# ADCMP607-step-gen.net
KiCad netlist of a schematic drawn in EAGLE
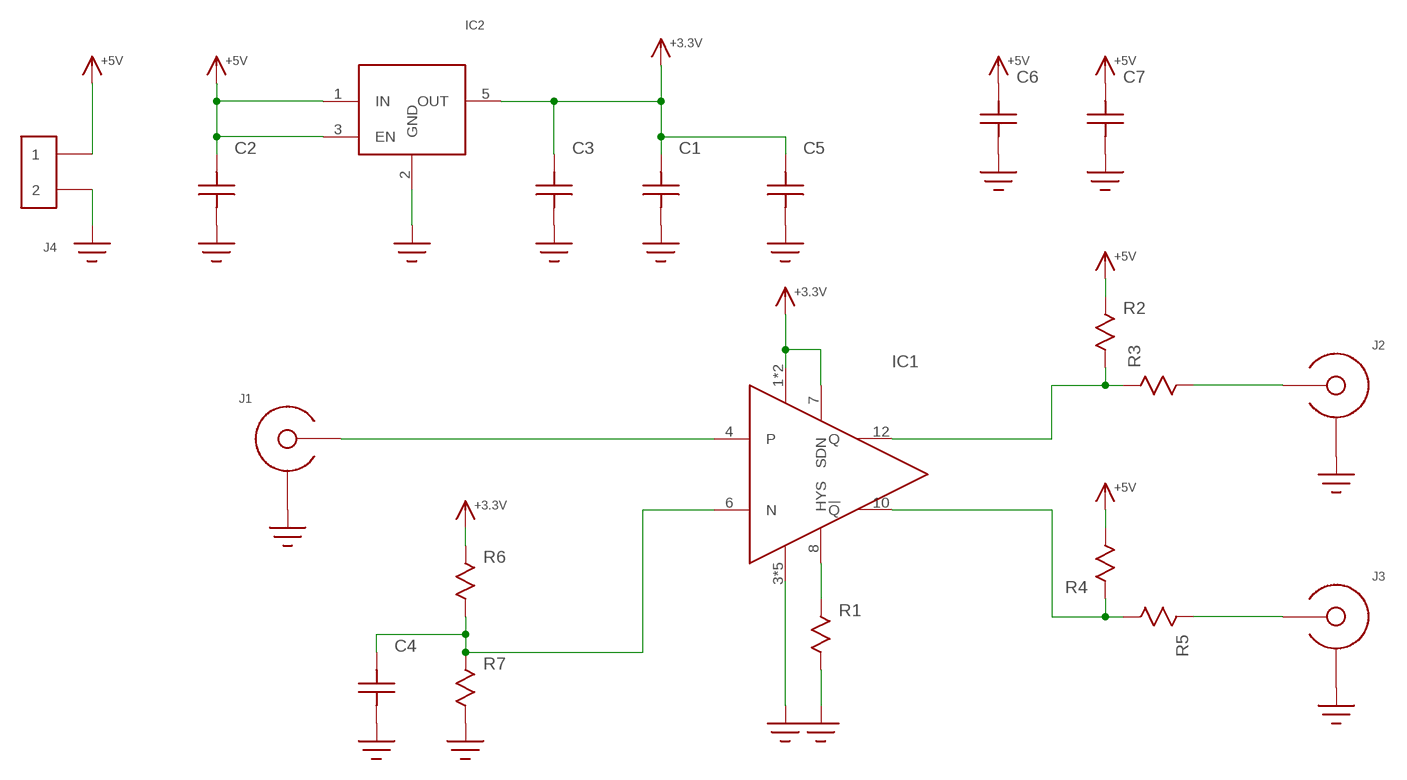
[diagram p0: schematic, sheet 1]

(export (version "E")
  (design (tool "Eeschema 10.0.6"))
  (components
    (comp (ref "C1") (value "C") (footprint "eagle-import:C0402") (libsource (lib "eagle-import") (part "C")))
    (comp (ref "C2")
      (value "C1206")
      (footprint "eagle-import:1206")
      (libsource (lib "eagle-import") (part "C1206"))
    )
    (comp (ref "C3")
      (value "C0603")
      (footprint "eagle-import:C0603")
      (libsource (lib "eagle-import") (part "C0603"))
    )
    (comp (ref "C4")
      (value "C0603")
      (footprint "eagle-import:C0603")
      (libsource (lib "eagle-import") (part "C0603"))
    )
    (comp (ref "C5") (value "C") (footprint "eagle-import:C0402") (libsource (lib "eagle-import") (part "C")))
    (comp (ref "C6") (value "C") (footprint "eagle-import:C0402") (libsource (lib "eagle-import") (part "C")))
    (comp (ref "C7") (value "C") (footprint "eagle-import:C0402") (libsource (lib "eagle-import") (part "C")))
    (comp (ref "IC1")
      (value "ADCMP607")
      (footprint "eagle-import:QFN12-3X3")
      (libsource (lib "eagle-import") (part "ADCMP607"))
    )
    (comp (ref "IC2")
      (value "MIC5501")
      (footprint "eagle-import:SOT23-5")
      (libsource (lib "eagle-import") (part "MIC5501"))
    )
    (comp (ref "J1")
      (value "SMA-EDGE-LAUNCH4L-4020-TAPER-FIXED")
      (footprint "eagle-import:SMA_EDGE_LAUNCH_4L_4020_TAPER_FIXED")
      (libsource (lib "eagle-import") (part "SMA-EDGE-LAUNCH4L-4020-TAPER-FIXED"))
    )
    (comp (ref "J2")
      (value "SMA-EDGE-LAUNCH4L-4020-TAPER-FIXED")
      (footprint "eagle-import:SMA_EDGE_LAUNCH_4L_4020_TAPER_FIXED")
      (libsource (lib "eagle-import") (part "SMA-EDGE-LAUNCH4L-4020-TAPER-FIXED"))
    )
    (comp (ref "J3")
      (value "SMA-EDGE-LAUNCH4L-4020-TAPER-FIXED")
      (footprint "eagle-import:SMA_EDGE_LAUNCH_4L_4020_TAPER_FIXED")
      (libsource (lib "eagle-import") (part "SMA-EDGE-LAUNCH4L-4020-TAPER-FIXED"))
    )
    (comp (ref "J4")
      (value "HEADER_2PIN")
      (footprint "eagle-import:HEADER_2PIN")
      (libsource (lib "eagle-import") (part "HEADER_2PIN"))
    )
    (comp (ref "R1")
      (value "R0603")
      (footprint "eagle-import:R0603")
      (libsource (lib "eagle-import") (part "R0603"))
    )
    (comp (ref "R2")
      (value "R0402")
      (footprint "eagle-import:0402")
      (libsource (lib "eagle-import") (part "R0402"))
    )
    (comp (ref "R3")
      (value "R0402")
      (footprint "eagle-import:0402")
      (libsource (lib "eagle-import") (part "R0402"))
    )
    (comp (ref "R4")
      (value "R0402")
      (footprint "eagle-import:0402")
      (libsource (lib "eagle-import") (part "R0402"))
    )
    (comp (ref "R5")
      (value "R0402")
      (footprint "eagle-import:0402")
      (libsource (lib "eagle-import") (part "R0402"))
    )
    (comp (ref "R6")
      (value "R0603")
      (footprint "eagle-import:R0603")
      (libsource (lib "eagle-import") (part "R0603"))
    )
    (comp (ref "R7")
      (value "R0603")
      (footprint "eagle-import:R0603")
      (libsource (lib "eagle-import") (part "R0603"))
    )
  )
  (nets
    (net (code "1") (name "+3.3V") (class "Default")
      (node (ref "C1") (pin "2") (pinfunction "P$2_2") (pintype "bidirectional"))
      (node (ref "C3") (pin "P$2") (pinfunction "P$2_P$2") (pintype "bidirectional"))
      (node (ref "C5") (pin "2") (pinfunction "P$2_2") (pintype "bidirectional"))
      (node (ref "IC1") (pin "1") (pinfunction "VCC_1") (pintype "bidirectional"))
      (node (ref "IC1") (pin "2") (pinfunction "VCC_2") (pintype "bidirectional"))
      (node (ref "IC1") (pin "7") (pinfunction "SDN_7") (pintype "bidirectional"))
      (node (ref "IC2") (pin "5") (pinfunction "OUT_5") (pintype "bidirectional"))
      (node (ref "R6") (pin "P$1") (pinfunction "P$3_P$1") (pintype "bidirectional"))
    )
    (net (code "2") (name "+5V") (class "Default")
      (node (ref "C2") (pin "P$2") (pinfunction "P$2_P$2") (pintype "bidirectional"))
      (node (ref "C6") (pin "2") (pinfunction "P$2_2") (pintype "bidirectional"))
      (node (ref "C7") (pin "2") (pinfunction "P$2_2") (pintype "bidirectional"))
      (node (ref "IC2") (pin "1") (pinfunction "IN_1") (pintype "bidirectional"))
      (node (ref "IC2") (pin "3") (pinfunction "EN_3") (pintype "bidirectional"))
      (node (ref "J4") (pin "1") (pinfunction "1_1") (pintype "bidirectional"))
      (node (ref "R2") (pin "1") (pinfunction "P$3_1") (pintype "bidirectional"))
      (node (ref "R4") (pin "2") (pinfunction "P$4_2") (pintype "bidirectional"))
    )
    (net (code "3") (name "GND") (class "Default")
      (node (ref "C1") (pin "1") (pinfunction "P$1_1") (pintype "bidirectional"))
      (node (ref "C2") (pin "P$1") (pinfunction "P$1_P$1") (pintype "bidirectional"))
      (node (ref "C3") (pin "P$1") (pinfunction "P$1_P$1") (pintype "bidirectional"))
      (node (ref "C4") (pin "P$1") (pinfunction "P$1_P$1") (pintype "bidirectional"))
      (node (ref "C5") (pin "1") (pinfunction "P$1_1") (pintype "bidirectional"))
      (node (ref "C6") (pin "1") (pinfunction "P$1_1") (pintype "bidirectional"))
      (node (ref "C7") (pin "1") (pinfunction "P$1_1") (pintype "bidirectional"))
      (node (ref "IC1") (pin "11") (pinfunction "VEE_11") (pintype "bidirectional"))
      (node (ref "IC1") (pin "3") (pinfunction "VEE_3") (pintype "bidirectional"))
      (node (ref "IC1") (pin "5") (pinfunction "VEE_5") (pintype "bidirectional"))
      (node (ref "IC1") (pin "9") (pinfunction "VEE_9") (pintype "bidirectional"))
      (node (ref "IC1") (pin "EP") (pinfunction "VEE_EP") (pintype "bidirectional"))
      (node (ref "IC2") (pin "2") (pinfunction "GND_2") (pintype "bidirectional"))
      (node (ref "J1") (pin "BOTTOM_GND") (pinfunction "SHIELD_BOTTOM_GND") (pintype "bidirectional"))
      (node (ref "J1") (pin "GND@1") (pinfunction "SHIELD_GND@1") (pintype "bidirectional"))
      (node (ref "J1") (pin "GND@14") (pinfunction "SHIELD_GND@14") (pintype "bidirectional"))
      (node (ref "J1") (pin "GND@15") (pinfunction "SHIELD_GND@15") (pintype "bidirectional"))
      (node (ref "J1") (pin "GND@16") (pinfunction "SHIELD_GND@16") (pintype "bidirectional"))
      (node (ref "J1") (pin "GND@17") (pinfunction "SHIELD_GND@17") (pintype "bidirectional"))
      (node (ref "J1") (pin "GND@2") (pinfunction "SHIELD_GND@2") (pintype "bidirectional"))
      (node (ref "J1") (pin "GND@3") (pinfunction "SHIELD_GND@3") (pintype "bidirectional"))
      (node (ref "J1") (pin "GND@4") (pinfunction "SHIELD_GND@4") (pintype "bidirectional"))
      (node (ref "J1") (pin "GND@5") (pinfunction "SHIELD_GND@5") (pintype "bidirectional"))
      (node (ref "J1") (pin "GND@6") (pinfunction "SHIELD_GND@6") (pintype "bidirectional"))
      (node (ref "J1") (pin "GND@7") (pinfunction "SHIELD_GND@7") (pintype "bidirectional"))
      (node (ref "J1") (pin "GND@8") (pinfunction "SHIELD_GND@8") (pintype "bidirectional"))
      (node (ref "J1") (pin "GND_PAD1") (pinfunction "SHIELD_GND_PAD1") (pintype "bidirectional"))
      (node (ref "J1") (pin "GND_PAD2") (pinfunction "SHIELD_GND_PAD2") (pintype "bidirectional"))
      (node (ref "J1") (pin "P$1") (pinfunction "SHIELD_P$1") (pintype "bidirectional"))
      (node (ref "J1") (pin "P$2") (pinfunction "SHIELD_P$2") (pintype "bidirectional"))
      (node (ref "J2") (pin "BOTTOM_GND") (pinfunction "SHIELD_BOTTOM_GND") (pintype "bidirectional"))
      (node (ref "J2") (pin "GND@1") (pinfunction "SHIELD_GND@1") (pintype "bidirectional"))
      (node (ref "J2") (pin "GND@14") (pinfunction "SHIELD_GND@14") (pintype "bidirectional"))
      (node (ref "J2") (pin "GND@15") (pinfunction "SHIELD_GND@15") (pintype "bidirectional"))
      (node (ref "J2") (pin "GND@16") (pinfunction "SHIELD_GND@16") (pintype "bidirectional"))
      (node (ref "J2") (pin "GND@17") (pinfunction "SHIELD_GND@17") (pintype "bidirectional"))
      (node (ref "J2") (pin "GND@2") (pinfunction "SHIELD_GND@2") (pintype "bidirectional"))
      (node (ref "J2") (pin "GND@3") (pinfunction "SHIELD_GND@3") (pintype "bidirectional"))
      (node (ref "J2") (pin "GND@4") (pinfunction "SHIELD_GND@4") (pintype "bidirectional"))
      (node (ref "J2") (pin "GND@5") (pinfunction "SHIELD_GND@5") (pintype "bidirectional"))
      (node (ref "J2") (pin "GND@6") (pinfunction "SHIELD_GND@6") (pintype "bidirectional"))
      (node (ref "J2") (pin "GND@7") (pinfunction "SHIELD_GND@7") (pintype "bidirectional"))
      (node (ref "J2") (pin "GND@8") (pinfunction "SHIELD_GND@8") (pintype "bidirectional"))
      (node (ref "J2") (pin "GND_PAD1") (pinfunction "SHIELD_GND_PAD1") (pintype "bidirectional"))
      (node (ref "J2") (pin "GND_PAD2") (pinfunction "SHIELD_GND_PAD2") (pintype "bidirectional"))
      (node (ref "J2") (pin "P$1") (pinfunction "SHIELD_P$1") (pintype "bidirectional"))
      (node (ref "J2") (pin "P$2") (pinfunction "SHIELD_P$2") (pintype "bidirectional"))
      (node (ref "J3") (pin "BOTTOM_GND") (pinfunction "SHIELD_BOTTOM_GND") (pintype "bidirectional"))
      (node (ref "J3") (pin "GND@1") (pinfunction "SHIELD_GND@1") (pintype "bidirectional"))
      (node (ref "J3") (pin "GND@14") (pinfunction "SHIELD_GND@14") (pintype "bidirectional"))
      (node (ref "J3") (pin "GND@15") (pinfunction "SHIELD_GND@15") (pintype "bidirectional"))
      (node (ref "J3") (pin "GND@16") (pinfunction "SHIELD_GND@16") (pintype "bidirectional"))
      (node (ref "J3") (pin "GND@17") (pinfunction "SHIELD_GND@17") (pintype "bidirectional"))
      (node (ref "J3") (pin "GND@2") (pinfunction "SHIELD_GND@2") (pintype "bidirectional"))
      (node (ref "J3") (pin "GND@3") (pinfunction "SHIELD_GND@3") (pintype "bidirectional"))
      (node (ref "J3") (pin "GND@4") (pinfunction "SHIELD_GND@4") (pintype "bidirectional"))
      (node (ref "J3") (pin "GND@5") (pinfunction "SHIELD_GND@5") (pintype "bidirectional"))
      (node (ref "J3") (pin "GND@6") (pinfunction "SHIELD_GND@6") (pintype "bidirectional"))
      (node (ref "J3") (pin "GND@7") (pinfunction "SHIELD_GND@7") (pintype "bidirectional"))
      (node (ref "J3") (pin "GND@8") (pinfunction "SHIELD_GND@8") (pintype "bidirectional"))
      (node (ref "J3") (pin "GND_PAD1") (pinfunction "SHIELD_GND_PAD1") (pintype "bidirectional"))
      (node (ref "J3") (pin "GND_PAD2") (pinfunction "SHIELD_GND_PAD2") (pintype "bidirectional"))
      (node (ref "J3") (pin "P$1") (pinfunction "SHIELD_P$1") (pintype "bidirectional"))
      (node (ref "J3") (pin "P$2") (pinfunction "SHIELD_P$2") (pintype "bidirectional"))
      (node (ref "J4") (pin "2") (pinfunction "2_2") (pintype "bidirectional"))
      (node (ref "R1") (pin "P$2") (pinfunction "P$4_P$2") (pintype "bidirectional"))
      (node (ref "R7") (pin "P$2") (pinfunction "P$4_P$2") (pintype "bidirectional"))
    )
    (net (code "4") (name "Net-(IC1-HYS)") (class "Default")
      (node (ref "IC1") (pin "8") (pinfunction "HYS_8") (pintype "bidirectional"))
      (node (ref "R1") (pin "P$1") (pinfunction "P$3_P$1") (pintype "bidirectional"))
    )
    (net (code "5") (name "Net-(IC1-N)") (class "Default")
      (node (ref "C4") (pin "P$2") (pinfunction "P$2_P$2") (pintype "bidirectional"))
      (node (ref "IC1") (pin "6") (pinfunction "N_6") (pintype "bidirectional"))
      (node (ref "R6") (pin "P$2") (pinfunction "P$4_P$2") (pintype "bidirectional"))
      (node (ref "R7") (pin "P$1") (pinfunction "P$3_P$1") (pintype "bidirectional"))
    )
    (net (code "6") (name "Net-(IC1-P)") (class "Default")
      (node (ref "IC1") (pin "4") (pinfunction "P_4") (pintype "bidirectional"))
      (node (ref "J1") (pin "CENTER@1") (pinfunction "CENTER_CENTER@1") (pintype "bidirectional"))
      (node (ref "J1") (pin "P$3") (pinfunction "CENTER_P$3") (pintype "bidirectional"))
    )
    (net (code "7") (name "Net-(IC1-Q)") (class "Default")
      (node (ref "IC1") (pin "12") (pinfunction "Q_12") (pintype "bidirectional"))
      (node (ref "R2") (pin "2") (pinfunction "P$4_2") (pintype "bidirectional"))
      (node (ref "R3") (pin "1") (pinfunction "P$3_1") (pintype "bidirectional"))
    )
    (net (code "8") (name "Net-(IC1-~{Q})") (class "Default")
      (node (ref "IC1") (pin "10") (pinfunction "~{Q}_10") (pintype "bidirectional"))
      (node (ref "R4") (pin "1") (pinfunction "P$3_1") (pintype "bidirectional"))
      (node (ref "R5") (pin "2") (pinfunction "P$4_2") (pintype "bidirectional"))
    )
    (net (code "9") (name "Net-(R3-P$4)") (class "Default")
      (node (ref "J2") (pin "CENTER@1") (pinfunction "CENTER_CENTER@1") (pintype "bidirectional"))
      (node (ref "J2") (pin "P$3") (pinfunction "CENTER_P$3") (pintype "bidirectional"))
      (node (ref "R3") (pin "2") (pinfunction "P$4_2") (pintype "bidirectional"))
    )
    (net (code "10") (name "Net-(R5-P$3)") (class "Default")
      (node (ref "J3") (pin "CENTER@1") (pinfunction "CENTER_CENTER@1") (pintype "bidirectional"))
      (node (ref "J3") (pin "P$3") (pinfunction "CENTER_P$3") (pintype "bidirectional"))
      (node (ref "R5") (pin "1") (pinfunction "P$3_1") (pintype "bidirectional"))
    )
  )
)
